# POWER.net
KiCad netlist of a schematic drawn in Altium Designer
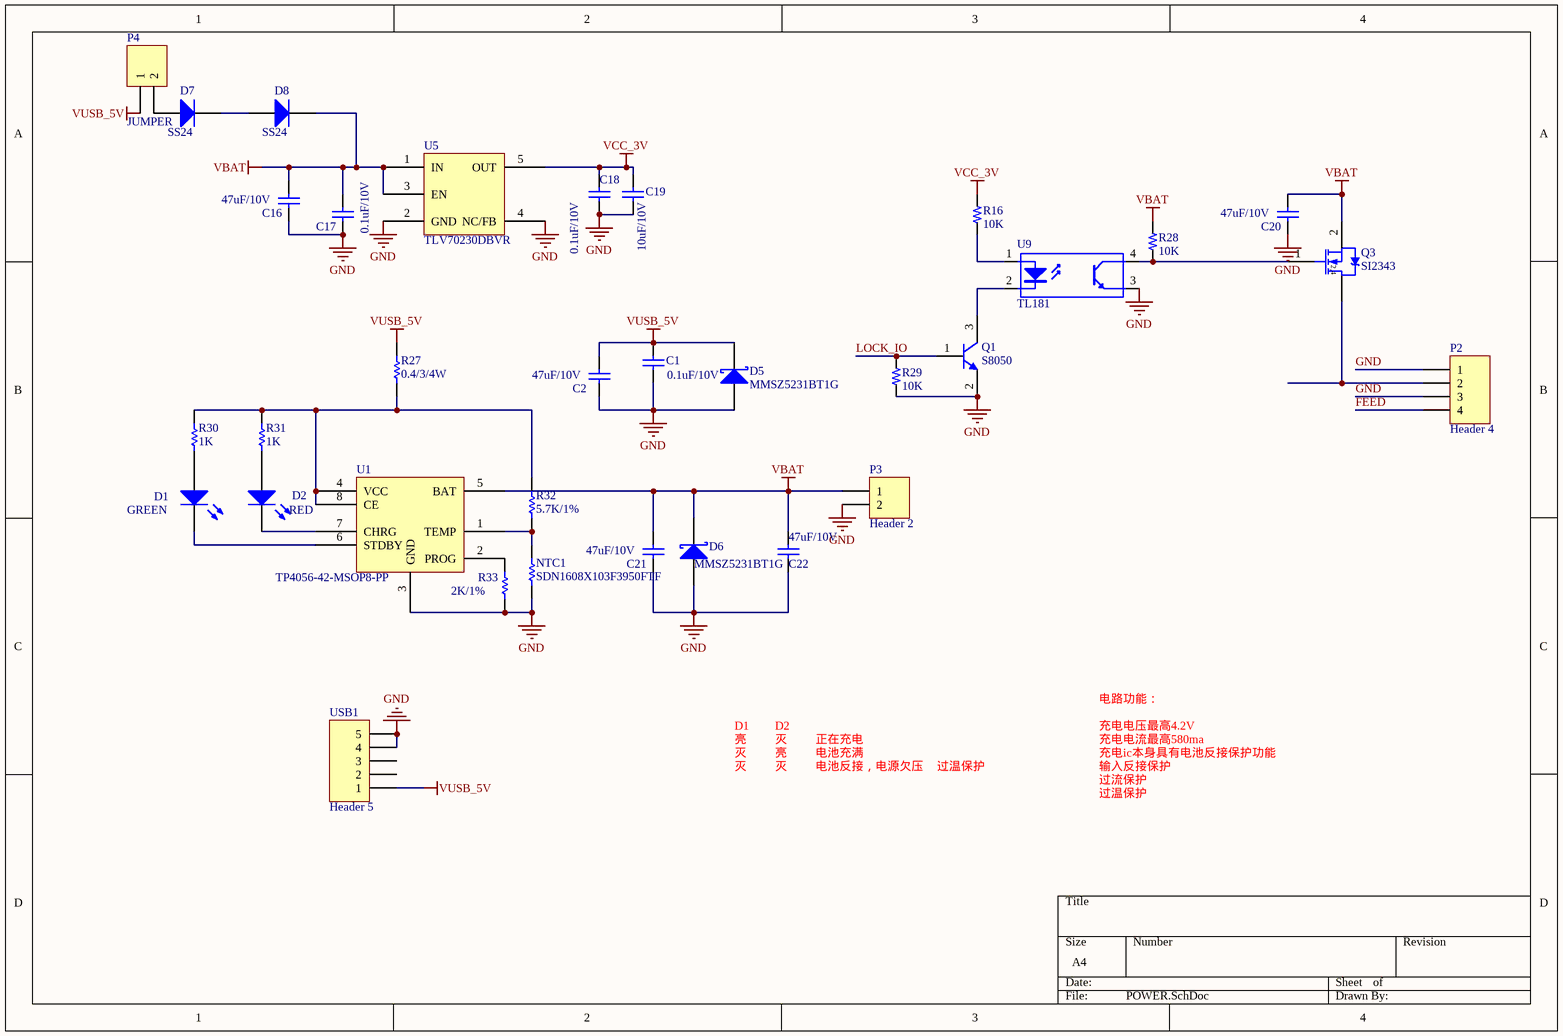
[diagram p0: POWER.SchDoc]

(export (version "E")
  (design (tool "Eeschema 10.0.6"))
  (components
    (comp (ref "C1")
      (value "0.1uF/10V")
      (footprint "0603C")
      (description "Capacitor")
      (fields (field (name "PUBLISHER") "Altium Limited"))
      (libsource (lib "Miscellaneous Devices") (part "Cap"))
    )
    (comp (ref "C2")
      (value "47uF/10V")
      (footprint "2220C")
      (description "Capacitor")
      (fields (field (name "PUBLISHER") "Altium Limited"))
      (libsource (lib "Miscellaneous Devices") (part "Cap"))
    )
    (comp (ref "C16")
      (value "47uF/10V")
      (footprint "2220C")
      (description "Capacitor")
      (fields (field (name "PUBLISHER") "Altium Limited"))
      (libsource (lib "Miscellaneous Devices") (part "Cap"))
    )
    (comp (ref "C17")
      (value "0.1uF/10V")
      (footprint "0603C")
      (description "Capacitor")
      (fields (field (name "PUBLISHER") "Altium Limited"))
      (libsource (lib "Miscellaneous Devices") (part "Cap"))
    )
    (comp (ref "C18")
      (value "0.1uF/10V")
      (footprint "0603C")
      (description "Capacitor")
      (fields (field (name "PUBLISHER") "Altium Limited"))
      (libsource (lib "Miscellaneous Devices") (part "Cap"))
    )
    (comp (ref "C19")
      (value "10uF/10V")
      (footprint "0603C")
      (description "Capacitor")
      (fields (field (name "PUBLISHER") "Altium Limited"))
      (libsource (lib "Miscellaneous Devices") (part "Cap"))
    )
    (comp (ref "C20")
      (value "47uF/10V")
      (footprint "2220C")
      (description "Capacitor")
      (fields (field (name "PUBLISHER") "Altium Limited"))
      (libsource (lib "Miscellaneous Devices") (part "Cap"))
    )
    (comp (ref "C21")
      (value "47uF/10V")
      (footprint "2220C")
      (description "Capacitor")
      (fields (field (name "PUBLISHER") "Altium Limited"))
      (libsource (lib "Miscellaneous Devices") (part "Cap"))
    )
    (comp (ref "C22")
      (value "47uF/10V")
      (footprint "2220C")
      (description "Capacitor")
      (fields (field (name "PUBLISHER") "Altium Limited"))
      (libsource (lib "Miscellaneous Devices") (part "Cap"))
    )
    (comp (ref "D1")
      (value "~")
      (footprint "0603LED")
      (description "Typical INFRARED GaAs LED")
      (fields (field (name "PUBLISHER") "GREEN"))
      (libsource (lib "Miscellaneous Devices") (part "LED0"))
    )
    (comp (ref "D2")
      (value "~")
      (footprint "0603LED")
      (description "Typical INFRARED GaAs LED")
      (fields (field (name "PUBLISHER") "RED"))
      (libsource (lib "Miscellaneous Devices") (part "LED0"))
    )
    (comp (ref "D5")
      (value "MMSZ5231BT1G")
      (footprint "SOD123")
      (description "Schottky Rectifier")
      (fields (field (name "PUBLISHER") "Altium Limited"))
      (libsource (lib "Miscellaneous Devices") (part "Diode 10TQ040"))
    )
    (comp (ref "D6")
      (value "MMSZ5231BT1G")
      (footprint "SOD123")
      (description "Schottky Rectifier")
      (fields (field (name "PUBLISHER") "Altium Limited"))
      (libsource (lib "Miscellaneous Devices") (part "Diode 10TQ040"))
    )
    (comp (ref "D7")
      (value "SS24")
      (footprint "SMA")
      (description "High Conductance Fast Diode")
      (fields (field (name "PUBLISHER") "Altium Limited"))
      (libsource (lib "Miscellaneous Devices") (part "Diode 1N4148"))
    )
    (comp (ref "D8")
      (value "SS24")
      (footprint "SMA")
      (description "High Conductance Fast Diode")
      (fields (field (name "PUBLISHER") "Altium Limited"))
      (libsource (lib "Miscellaneous Devices") (part "Diode 1N4148"))
    )
    (comp (ref "NTC1")
      (value "SDN1608X103F3950FTF")
      (footprint "0603R")
      (description "Semiconductor Resistor")
      (fields (field (name "PUBLISHER") "Altium Limited"))
      (libsource (lib "Miscellaneous Devices") (part "Res Semi"))
    )
    (comp (ref "P2")
      (value "Header 4")
      (footprint "HDR1X4")
      (description "Header, 4-Pin")
      (fields (field (name "PUBLISHER") "Altium Limited"))
      (libsource (lib "Miscellaneous Connectors") (part "Header 4"))
    )
    (comp (ref "P3")
      (value "Header 2")
      (footprint "2X2.54MMZ")
      (description "Header, 2-Pin")
      (fields (field (name "PUBLISHER") "Altium Limited"))
      (libsource (lib "Miscellaneous Connectors") (part "Header 2"))
    )
    (comp (ref "P4")
      (value "JUMPER")
      (footprint "HDR1X2")
      (description "Header, 2-Pin")
      (fields (field (name "PUBLISHER") "Altium Limited"))
      (libsource (lib "") (part "Header 2_1"))
    )
    (comp (ref "Q1") (value "S8050") (footprint "SOT23-3") (libsource (lib "Schlib1") (part "NPN")))
    (comp (ref "Q3")
      (value "SI2343")
      (footprint "SOT23-3")
      (description "BUK92150-55A")
      (fields (field (name "PUBLISHER") "Altium Limited"))
      (libsource (lib "Schlib1") (part "BUK92150-55A"))
    )
    (comp (ref "R16")
      (value "10K")
      (footprint "0603R")
      (description "R")
      (libsource (lib "JRJ_1") (part "R"))
    )
    (comp (ref "R27")
      (value "0.4/3/4W")
      (footprint "2010R")
      (description "Semiconductor Resistor")
      (fields (field (name "PUBLISHER") "Altium Limited"))
      (libsource (lib "Miscellaneous Devices") (part "Res Semi"))
    )
    (comp (ref "R28")
      (value "10K")
      (footprint "0603R")
      (description "R")
      (libsource (lib "JRJ_1") (part "R"))
    )
    (comp (ref "R29")
      (value "10K")
      (footprint "0603R")
      (description "R")
      (libsource (lib "JRJ_1") (part "R"))
    )
    (comp (ref "R30")
      (value "1K")
      (footprint "0603R")
      (description "Semiconductor Resistor")
      (fields (field (name "PUBLISHER") "Altium Limited"))
      (libsource (lib "Miscellaneous Devices") (part "Res Semi"))
    )
    (comp (ref "R31")
      (value "1K")
      (footprint "0603R")
      (description "Semiconductor Resistor")
      (fields (field (name "PUBLISHER") "Altium Limited"))
      (libsource (lib "Miscellaneous Devices") (part "Res Semi"))
    )
    (comp (ref "R32")
      (value "5.7K/1%")
      (footprint "0603R")
      (description "Semiconductor Resistor")
      (fields (field (name "PUBLISHER") "Altium Limited"))
      (libsource (lib "Miscellaneous Devices") (part "Res Semi"))
    )
    (comp (ref "R33")
      (value "2K/1%")
      (footprint "0603R")
      (description "Semiconductor Resistor")
      (fields (field (name "PUBLISHER") "Altium Limited"))
      (libsource (lib "Miscellaneous Devices") (part "Res Semi"))
    )
    (comp (ref "U1")
      (value "TP4056-42-MSOP8-PP")
      (footprint "SOP65P490X265-8N")
      (libsource (lib "CHARGER") (part "TP4056"))
    )
    (comp (ref "U5")
      (value "TLV70230DBVR")
      (footprint "SOT23-5(DBV)")
      (libsource (lib "Schlib_20110825") (part "TLV70230DBVR"))
    )
    (comp (ref "U9")
      (value "TL181")
      (footprint "DIP-4")
      (description "4-Pin Phototransistor Optocoupler")
      (fields (field (name "PUBLISHER") "Altium Limited"))
      (libsource (lib "Miscellaneous Devices") (part "Optoisolator1"))
    )
    (comp (ref "USB1")
      (value "Header 5")
      (footprint "USB-A")
      (description "Header, 5-Pin")
      (fields (field (name "PUBLISHER") "Altium Limited"))
      (libsource (lib "Miscellaneous Connectors") (part "Header 5"))
    )
  )
  (nets
    (net (code "1") (name "/FEED") (class "Default")
      (node (ref "P2") (pin "4") (pinfunction "4_4") (pintype "passive"))
    )
    (net (code "2") (name "/LOCK_IO") (class "Default")
      (node (ref "Q1") (pin "1") (pinfunction "B_1") (pintype "passive"))
      (node (ref "R29") (pin "2") (pintype "passive"))
    )
    (net (code "3") (name "GND") (class "Default")
      (node (ref "C1") (pin "1") (pinfunction "1_1") (pintype "passive"))
      (node (ref "C16") (pin "1") (pinfunction "1_1") (pintype "passive"))
      (node (ref "C17") (pin "2") (pinfunction "2_2") (pintype "passive"))
      (node (ref "C18") (pin "2") (pinfunction "2_2") (pintype "passive"))
      (node (ref "C19") (pin "1") (pinfunction "1_1") (pintype "passive"))
      (node (ref "C2") (pin "1") (pinfunction "1_1") (pintype "passive"))
      (node (ref "C20") (pin "1") (pinfunction "1_1") (pintype "passive"))
      (node (ref "C21") (pin "1") (pinfunction "1_1") (pintype "passive"))
      (node (ref "C22") (pin "1") (pinfunction "1_1") (pintype "passive"))
      (node (ref "D5") (pin "A") (pinfunction "A_A") (pintype "passive"))
      (node (ref "D6") (pin "A") (pinfunction "A_A") (pintype "passive"))
      (node (ref "NTC1") (pin "2") (pinfunction "2_2") (pintype "passive"))
      (node (ref "P2") (pin "1") (pinfunction "1_1") (pintype "passive"))
      (node (ref "P2") (pin "3") (pinfunction "3_3") (pintype "passive"))
      (node (ref "P3") (pin "2") (pinfunction "2_2") (pintype "passive"))
      (node (ref "Q1") (pin "2") (pinfunction "E_2") (pintype "passive"))
      (node (ref "R29") (pin "1") (pintype "passive"))
      (node (ref "R33") (pin "1") (pinfunction "1_1") (pintype "passive"))
      (node (ref "U1") (pin "3") (pinfunction "GND_3") (pintype "passive"))
      (node (ref "U5") (pin "2") (pinfunction "GND_2") (pintype "passive"))
      (node (ref "U5") (pin "4") (pinfunction "NC/FB_4") (pintype "passive"))
      (node (ref "U9") (pin "3") (pinfunction "E_3") (pintype "passive"))
      (node (ref "USB1") (pin "4") (pinfunction "4_4") (pintype "passive"))
      (node (ref "USB1") (pin "5") (pinfunction "5_5") (pintype "passive"))
    )
    (net (code "4") (name "Net-(D1-A)") (class "Default")
      (node (ref "D1") (pin "1") (pinfunction "A_1") (pintype "passive"))
      (node (ref "R30") (pin "1") (pinfunction "1_1") (pintype "passive"))
    )
    (net (code "5") (name "Net-(D1-K)") (class "Default")
      (node (ref "D1") (pin "2") (pinfunction "K_2") (pintype "passive"))
      (node (ref "U1") (pin "6") (pinfunction "STDBY_6") (pintype "passive"))
    )
    (net (code "6") (name "Net-(D2-A)") (class "Default")
      (node (ref "D2") (pin "1") (pinfunction "A_1") (pintype "passive"))
      (node (ref "R31") (pin "1") (pinfunction "1_1") (pintype "passive"))
    )
    (net (code "7") (name "Net-(D2-K)") (class "Default")
      (node (ref "D2") (pin "2") (pinfunction "K_2") (pintype "passive"))
      (node (ref "U1") (pin "7") (pinfunction "CHRG_7") (pintype "passive"))
    )
    (net (code "8") (name "Net-(D7-A)") (class "Default")
      (node (ref "D7") (pin "1") (pinfunction "A_1") (pintype "passive"))
      (node (ref "P4") (pin "2") (pinfunction "2_2") (pintype "passive"))
    )
    (net (code "9") (name "Net-(D7-K)") (class "Default")
      (node (ref "D7") (pin "2") (pinfunction "K_2") (pintype "passive"))
      (node (ref "D8") (pin "1") (pinfunction "A_1") (pintype "passive"))
    )
    (net (code "10") (name "Net-(Q1-C)") (class "Default")
      (node (ref "Q1") (pin "3") (pinfunction "C_3") (pintype "passive"))
      (node (ref "U9") (pin "2") (pinfunction "K_2") (pintype "passive"))
    )
    (net (code "11") (name "Net-(Q3-D)") (class "Default")
      (node (ref "P2") (pin "2") (pinfunction "2_2") (pintype "passive"))
      (node (ref "Q3") (pin "3") (pinfunction "D_3") (pintype "passive"))
    )
    (net (code "12") (name "Net-(Q3-G)") (class "Default")
      (node (ref "Q3") (pin "1") (pinfunction "G_1") (pintype "passive"))
      (node (ref "R28") (pin "1") (pintype "passive"))
      (node (ref "U9") (pin "4") (pinfunction "C_4") (pintype "passive"))
    )
    (net (code "13") (name "Net-(U1-CE)") (class "Default")
      (node (ref "R27") (pin "2") (pinfunction "2_2") (pintype "passive"))
      (node (ref "R30") (pin "2") (pinfunction "2_2") (pintype "passive"))
      (node (ref "R31") (pin "2") (pinfunction "2_2") (pintype "passive"))
      (node (ref "R32") (pin "1") (pinfunction "1_1") (pintype "passive"))
      (node (ref "U1") (pin "4") (pinfunction "VCC_4") (pintype "passive"))
      (node (ref "U1") (pin "8") (pinfunction "CE_8") (pintype "passive"))
    )
    (net (code "14") (name "Net-(U1-PROG)") (class "Default")
      (node (ref "R33") (pin "2") (pinfunction "2_2") (pintype "passive"))
      (node (ref "U1") (pin "2") (pinfunction "PROG_2") (pintype "passive"))
    )
    (net (code "15") (name "Net-(U1-TEMP)") (class "Default")
      (node (ref "NTC1") (pin "1") (pinfunction "1_1") (pintype "passive"))
      (node (ref "R32") (pin "2") (pinfunction "2_2") (pintype "passive"))
      (node (ref "U1") (pin "1") (pinfunction "TEMP_1") (pintype "passive"))
    )
    (net (code "16") (name "Net-(U9-A)") (class "Default")
      (node (ref "R16") (pin "1") (pintype "passive"))
      (node (ref "U9") (pin "1") (pinfunction "A_1") (pintype "passive"))
    )
    (net (code "17") (name "VBAT") (class "Default")
      (node (ref "C16") (pin "2") (pinfunction "2_2") (pintype "passive"))
      (node (ref "C17") (pin "1") (pinfunction "1_1") (pintype "passive"))
      (node (ref "C20") (pin "2") (pinfunction "2_2") (pintype "passive"))
      (node (ref "C21") (pin "2") (pinfunction "2_2") (pintype "passive"))
      (node (ref "C22") (pin "2") (pinfunction "2_2") (pintype "passive"))
      (node (ref "D6") (pin "K") (pinfunction "K_K") (pintype "passive"))
      (node (ref "D8") (pin "2") (pinfunction "K_2") (pintype "passive"))
      (node (ref "P3") (pin "1") (pinfunction "1_1") (pintype "passive"))
      (node (ref "Q3") (pin "2") (pinfunction "S_2") (pintype "passive"))
      (node (ref "R28") (pin "2") (pintype "passive"))
      (node (ref "U1") (pin "5") (pinfunction "BAT_5") (pintype "passive"))
      (node (ref "U5") (pin "1") (pinfunction "IN_1") (pintype "passive"))
      (node (ref "U5") (pin "3") (pinfunction "EN_3") (pintype "passive"))
    )
    (net (code "18") (name "VCC_3V") (class "Default")
      (node (ref "C18") (pin "1") (pinfunction "1_1") (pintype "passive"))
      (node (ref "C19") (pin "2") (pinfunction "2_2") (pintype "passive"))
      (node (ref "R16") (pin "2") (pintype "passive"))
      (node (ref "U5") (pin "5") (pinfunction "OUT_5") (pintype "passive"))
    )
    (net (code "19") (name "VUSB_5V") (class "Default")
      (node (ref "C1") (pin "2") (pinfunction "2_2") (pintype "passive"))
      (node (ref "C2") (pin "2") (pinfunction "2_2") (pintype "passive"))
      (node (ref "D5") (pin "K") (pinfunction "K_K") (pintype "passive"))
      (node (ref "P4") (pin "1") (pinfunction "1_1") (pintype "passive"))
      (node (ref "R27") (pin "1") (pinfunction "1_1") (pintype "passive"))
      (node (ref "USB1") (pin "1") (pinfunction "1_1") (pintype "passive"))
    )
    (net (code "20") (name "unconnected-(USB1-Pad2)") (class "Default")
      (node (ref "USB1") (pin "2") (pinfunction "2_2") (pintype "passive"))
    )
    (net (code "21") (name "unconnected-(USB1-Pad3)") (class "Default")
      (node (ref "USB1") (pin "3") (pinfunction "3_3") (pintype "passive"))
    )
  )
)
